# shield_lcd1.net
KiCad netlist of a schematic drawn in EAGLE
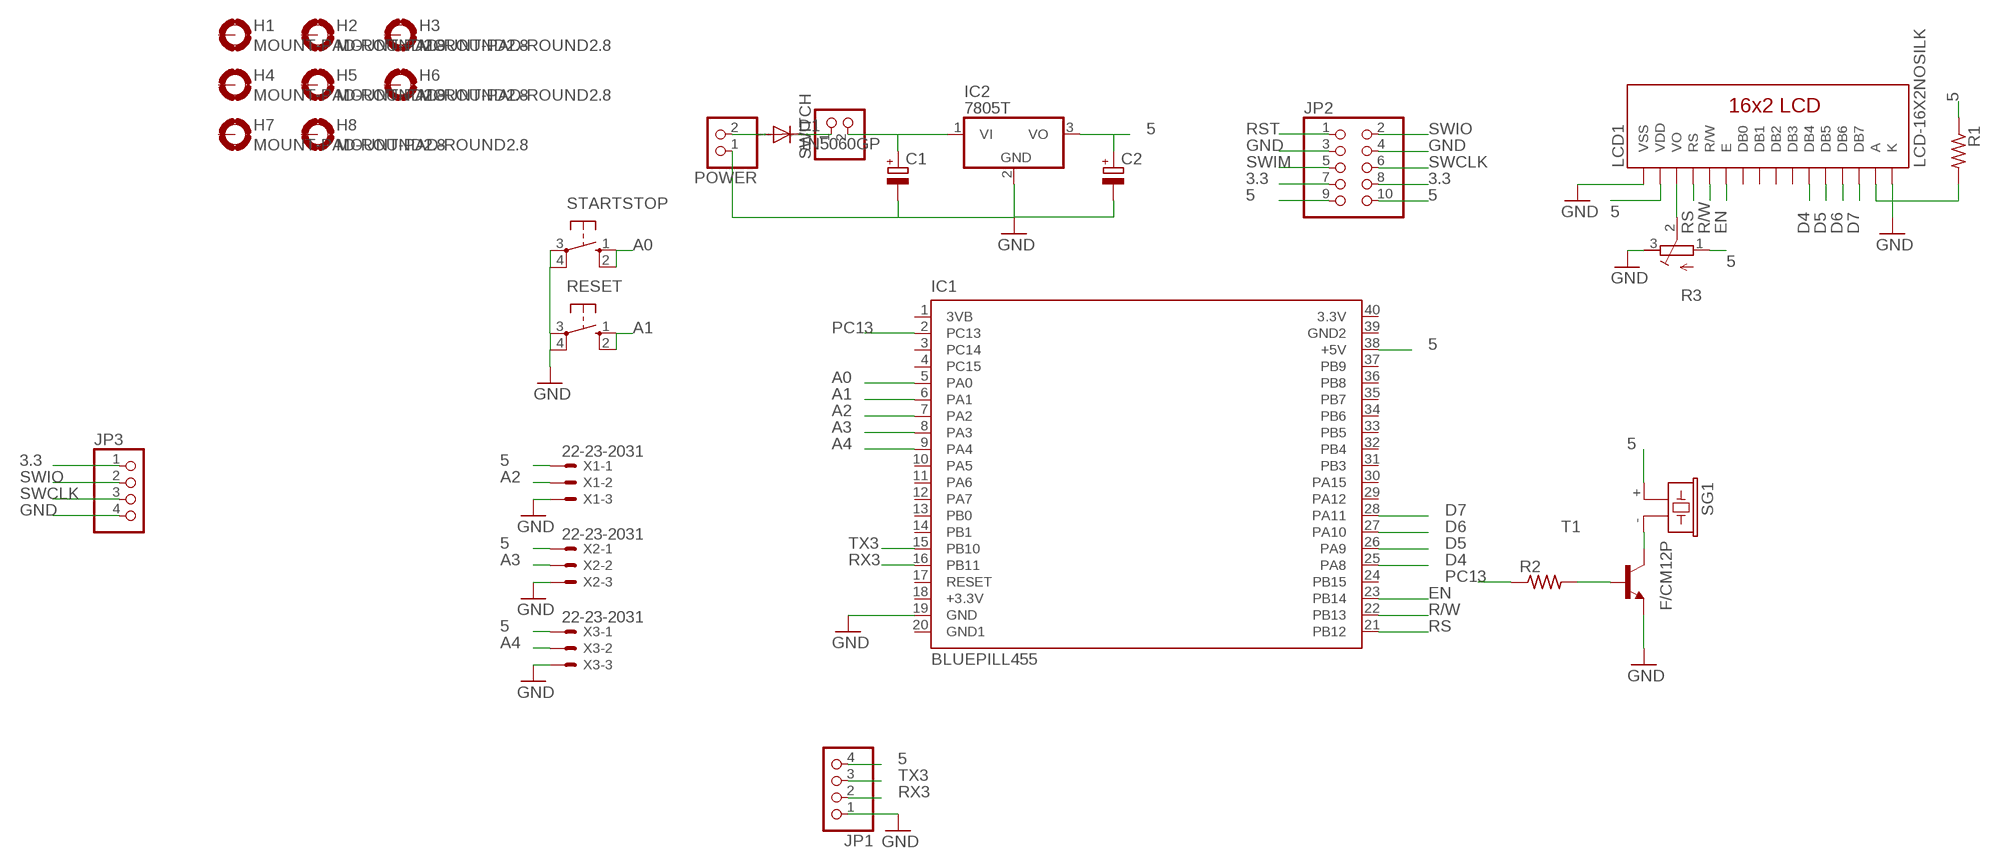
[diagram p0: schematic, sheet 1]

(export (version "E")
  (design (tool "Eeschema 10.0.6"))
  (components
    (comp (ref "C1")
      (value "CPOL-EUE2.5-7")
      (footprint "eagle-import:E2,5-7")
      (libsource (lib "eagle-import") (part "CPOL-EUE2.5-7"))
    )
    (comp (ref "C2")
      (value "CPOL-EUE2.5-6")
      (footprint "eagle-import:E2,5-6")
      (libsource (lib "eagle-import") (part "CPOL-EUE2.5-6"))
    )
    (comp (ref "D1")
      (value "1N5060GP")
      (footprint "eagle-import:DO15-12")
      (libsource (lib "eagle-import") (part "1N5060GP"))
    )
    (comp (ref "H1")
      (value "MOUNT-PAD-ROUND2.8")
      (footprint "eagle-import:2,8-PAD")
      (libsource (lib "eagle-import") (part "MOUNT-PAD-ROUND2.8"))
    )
    (comp (ref "H2")
      (value "MOUNT-PAD-ROUND2.8")
      (footprint "eagle-import:2,8-PAD")
      (libsource (lib "eagle-import") (part "MOUNT-PAD-ROUND2.8"))
    )
    (comp (ref "H3")
      (value "MOUNT-PAD-ROUND2.8")
      (footprint "eagle-import:2,8-PAD")
      (libsource (lib "eagle-import") (part "MOUNT-PAD-ROUND2.8"))
    )
    (comp (ref "H4")
      (value "MOUNT-PAD-ROUND2.8")
      (footprint "eagle-import:2,8-PAD")
      (libsource (lib "eagle-import") (part "MOUNT-PAD-ROUND2.8"))
    )
    (comp (ref "H5")
      (value "MOUNT-PAD-ROUND2.8")
      (footprint "eagle-import:2,8-PAD")
      (libsource (lib "eagle-import") (part "MOUNT-PAD-ROUND2.8"))
    )
    (comp (ref "H6")
      (value "MOUNT-PAD-ROUND2.8")
      (footprint "eagle-import:2,8-PAD")
      (libsource (lib "eagle-import") (part "MOUNT-PAD-ROUND2.8"))
    )
    (comp (ref "H7")
      (value "MOUNT-PAD-ROUND2.8")
      (footprint "eagle-import:2,8-PAD")
      (libsource (lib "eagle-import") (part "MOUNT-PAD-ROUND2.8"))
    )
    (comp (ref "H8")
      (value "MOUNT-PAD-ROUND2.8")
      (footprint "eagle-import:2,8-PAD")
      (libsource (lib "eagle-import") (part "MOUNT-PAD-ROUND2.8"))
    )
    (comp (ref "IC1")
      (value "BLUEPILL455")
      (footprint "eagle-import:DIL40")
      (fields (field (name "MF") "BluePill"))
      (libsource (lib "eagle-import") (part "BLUEPILL455"))
    )
    (comp (ref "IC2")
      (value "7805T")
      (footprint "eagle-import:TO220H")
      (libsource (lib "eagle-import") (part "78T05"))
    )
    (comp (ref "JP1")
      (value "PINHD-1X4")
      (footprint "eagle-import:1X04")
      (libsource (lib "eagle-import") (part "PINHD-1X4"))
    )
    (comp (ref "JP2")
      (value "PINHD-2X5")
      (footprint "eagle-import:2X05")
      (libsource (lib "eagle-import") (part "PINHD-2X5"))
    )
    (comp (ref "JP3")
      (value "PINHD-1X4")
      (footprint "eagle-import:1X04")
      (libsource (lib "eagle-import") (part "PINHD-1X4"))
    )
    (comp (ref "LCD1")
      (value "LCD-16X2NOSILK")
      (footprint "eagle-import:LCD-16X2_NOSILK")
      (libsource (lib "eagle-import") (part "LCD-16X2NOSILK"))
    )
    (comp (ref "POWER")
      (value "PINHD-1X2")
      (footprint "eagle-import:1X02")
      (libsource (lib "eagle-import") (part "PINHD-1X2"))
    )
    (comp (ref "R1")
      (value "R-US_0207/10")
      (footprint "eagle-import:0207_10")
      (libsource (lib "eagle-import") (part "R-US_0207/10"))
    )
    (comp (ref "R2")
      (value "R-US_M0805")
      (footprint "eagle-import:M0805")
      (libsource (lib "eagle-import") (part "R-US_M0805"))
    )
    (comp (ref "R3")
      (value "R-TRIMM3339P")
      (footprint "eagle-import:RTRIM3339P")
      (libsource (lib "eagle-import") (part "R-TRIMM3339P"))
    )
    (comp (ref "RESET")
      (value "40-XX")
      (footprint "eagle-import:B3F-40XX")
      (fields (field (name "MF") "OMRON COMPONENTS USA") (field (name "MPN") "B3F-4000"))
      (libsource (lib "eagle-import") (part "40-XX"))
    )
    (comp (ref "SG1")
      (value "F/CM12P")
      (footprint "eagle-import:F_CM12P")
      (libsource (lib "eagle-import") (part "F/CM12P"))
    )
    (comp (ref "STARTSTOP")
      (value "40-XX")
      (footprint "eagle-import:B3F-40XX")
      (fields (field (name "MF") "OMRON COMPONENTS USA") (field (name "MPN") "B3F-4000"))
      (libsource (lib "eagle-import") (part "40-XX"))
    )
    (comp (ref "SWITCH")
      (value "PINHD-1X2")
      (footprint "eagle-import:1X02")
      (libsource (lib "eagle-import") (part "PINHD-1X2"))
    )
    (comp (ref "T1")
      (value "BF820-NPN-SOT23-BEC")
      (footprint "eagle-import:SOT23-BEC")
      (libsource (lib "eagle-import") (part "-NPN-SOT23-BECBF820"))
    )
    (comp (ref "X1")
      (value "22-23-2031")
      (footprint "eagle-import:22-23-2031")
      (fields (field (name "MF") "MOLEX"))
      (libsource (lib "eagle-import") (part "22-23-2031"))
    )
    (comp (ref "X2")
      (value "22-23-2031")
      (footprint "eagle-import:22-23-2031")
      (fields (field (name "MF") "MOLEX"))
      (libsource (lib "eagle-import") (part "22-23-2031"))
    )
    (comp (ref "X3")
      (value "22-23-2031")
      (footprint "eagle-import:22-23-2031")
      (fields (field (name "MF") "MOLEX"))
      (libsource (lib "eagle-import") (part "22-23-2031"))
    )
  )
  (nets
    (net (code "1") (name "/3.3") (class "Default")
      (node (ref "JP2") (pin "7") (pinfunction "7_7") (pintype "passive"))
      (node (ref "JP2") (pin "8") (pinfunction "8_8") (pintype "passive"))
      (node (ref "JP3") (pin "1") (pinfunction "1_1") (pintype "passive"))
    )
    (net (code "2") (name "/5") (class "Default")
      (node (ref "C2") (pin "+") (pinfunction "+_+") (pintype "passive"))
      (node (ref "IC1") (pin "38") (pinfunction "+5V_38") (pintype "bidirectional"))
      (node (ref "IC2") (pin "3") (pinfunction "VO_3") (pintype "passive"))
      (node (ref "JP1") (pin "4") (pinfunction "4_4") (pintype "passive"))
      (node (ref "JP2") (pin "10") (pinfunction "10_10") (pintype "passive"))
      (node (ref "JP2") (pin "9") (pinfunction "9_9") (pintype "passive"))
      (node (ref "LCD1") (pin "2") (pinfunction "VDD_2") (pintype "power_in"))
      (node (ref "R1") (pin "1") (pinfunction "1_1") (pintype "passive"))
      (node (ref "R3") (pin "1") (pinfunction "A_1") (pintype "passive"))
      (node (ref "SG1") (pin "+") (pinfunction "1_+") (pintype "passive"))
      (node (ref "X1") (pin "1") (pinfunction "S_1") (pintype "passive"))
      (node (ref "X2") (pin "1") (pinfunction "S_1") (pintype "passive"))
      (node (ref "X3") (pin "1") (pinfunction "S_1") (pintype "passive"))
    )
    (net (code "3") (name "/A0") (class "Default")
      (node (ref "IC1") (pin "5") (pinfunction "PA0_5") (pintype "bidirectional"))
      (node (ref "STARTSTOP") (pin "1") (pinfunction "S_1") (pintype "passive"))
      (node (ref "STARTSTOP") (pin "2") (pinfunction "S1_2") (pintype "passive"))
    )
    (net (code "4") (name "/A1") (class "Default")
      (node (ref "IC1") (pin "6") (pinfunction "PA1_6") (pintype "bidirectional"))
      (node (ref "RESET") (pin "1") (pinfunction "S_1") (pintype "passive"))
      (node (ref "RESET") (pin "2") (pinfunction "S1_2") (pintype "passive"))
    )
    (net (code "5") (name "/A2") (class "Default")
      (node (ref "IC1") (pin "7") (pinfunction "PA2_7") (pintype "bidirectional"))
      (node (ref "X1") (pin "2") (pinfunction "S_2") (pintype "passive"))
    )
    (net (code "6") (name "/A3") (class "Default")
      (node (ref "IC1") (pin "8") (pinfunction "PA3_8") (pintype "bidirectional"))
      (node (ref "X2") (pin "2") (pinfunction "S_2") (pintype "passive"))
    )
    (net (code "7") (name "/A4") (class "Default")
      (node (ref "IC1") (pin "9") (pinfunction "PA4_9") (pintype "bidirectional"))
      (node (ref "X3") (pin "2") (pinfunction "S_2") (pintype "passive"))
    )
    (net (code "8") (name "/D4") (class "Default")
      (node (ref "IC1") (pin "25") (pinfunction "PA8_25") (pintype "bidirectional"))
      (node (ref "LCD1") (pin "11") (pinfunction "DB4_11") (pintype "bidirectional"))
    )
    (net (code "9") (name "/D5") (class "Default")
      (node (ref "IC1") (pin "26") (pinfunction "PA9_26") (pintype "bidirectional"))
      (node (ref "LCD1") (pin "12") (pinfunction "DB5_12") (pintype "bidirectional"))
    )
    (net (code "10") (name "/D6") (class "Default")
      (node (ref "IC1") (pin "27") (pinfunction "PA10_27") (pintype "bidirectional"))
      (node (ref "LCD1") (pin "13") (pinfunction "DB6_13") (pintype "bidirectional"))
    )
    (net (code "11") (name "/D7") (class "Default")
      (node (ref "IC1") (pin "28") (pinfunction "PA11_28") (pintype "bidirectional"))
      (node (ref "LCD1") (pin "14") (pinfunction "DB7_14") (pintype "bidirectional"))
    )
    (net (code "12") (name "/EN") (class "Default")
      (node (ref "IC1") (pin "23") (pinfunction "PB14_23") (pintype "bidirectional"))
      (node (ref "LCD1") (pin "6") (pinfunction "E_6") (pintype "input"))
    )
    (net (code "13") (name "/PA6") (class "Default")
      (node (ref "IC1") (pin "11") (pinfunction "PA6_11") (pintype "power_in"))
    )
    (net (code "14") (name "/PA7") (class "Default")
      (node (ref "IC1") (pin "12") (pinfunction "PA7_12") (pintype "power_in"))
    )
    (net (code "15") (name "/PB3") (class "Default")
      (node (ref "IC1") (pin "31") (pinfunction "PB3_31") (pintype "power_in"))
    )
    (net (code "16") (name "/PB4") (class "Default")
      (node (ref "IC1") (pin "32") (pinfunction "PB4_32") (pintype "power_in"))
    )
    (net (code "17") (name "/PC13") (class "Default")
      (node (ref "IC1") (pin "2") (pinfunction "PC13_2") (pintype "bidirectional"))
      (node (ref "R2") (pin "1") (pinfunction "1_1") (pintype "passive"))
    )
    (net (code "18") (name "/RS") (class "Default")
      (node (ref "IC1") (pin "21") (pinfunction "PB12_21") (pintype "bidirectional"))
      (node (ref "LCD1") (pin "4") (pinfunction "RS_4") (pintype "input"))
    )
    (net (code "19") (name "/RST") (class "Default")
      (node (ref "JP2") (pin "1") (pinfunction "1_1") (pintype "passive"))
    )
    (net (code "20") (name "/RX3") (class "Default")
      (node (ref "IC1") (pin "16") (pinfunction "PB11_16") (pintype "bidirectional"))
      (node (ref "JP1") (pin "2") (pinfunction "2_2") (pintype "passive"))
    )
    (net (code "21") (name "/R{slash}W") (class "Default")
      (node (ref "IC1") (pin "22") (pinfunction "PB13_22") (pintype "bidirectional"))
      (node (ref "LCD1") (pin "5") (pinfunction "R/W_5") (pintype "input"))
    )
    (net (code "22") (name "/SWCLK") (class "Default")
      (node (ref "JP2") (pin "6") (pinfunction "6_6") (pintype "passive"))
      (node (ref "JP3") (pin "3") (pinfunction "3_3") (pintype "passive"))
    )
    (net (code "23") (name "/SWIM") (class "Default")
      (node (ref "JP2") (pin "5") (pinfunction "5_5") (pintype "passive"))
    )
    (net (code "24") (name "/SWIO") (class "Default")
      (node (ref "JP2") (pin "2") (pinfunction "2_2") (pintype "passive"))
      (node (ref "JP3") (pin "2") (pinfunction "2_2") (pintype "passive"))
    )
    (net (code "25") (name "/TX3") (class "Default")
      (node (ref "IC1") (pin "15") (pinfunction "PB10_15") (pintype "bidirectional"))
      (node (ref "JP1") (pin "3") (pinfunction "3_3") (pintype "passive"))
    )
    (net (code "26") (name "GND") (class "Default")
      (node (ref "C1") (pin "-") (pinfunction "-_-") (pintype "passive"))
      (node (ref "C2") (pin "-") (pinfunction "-_-") (pintype "passive"))
      (node (ref "IC1") (pin "19") (pinfunction "GND_19") (pintype "bidirectional"))
      (node (ref "IC2") (pin "2") (pinfunction "GND_2") (pintype "passive"))
      (node (ref "JP1") (pin "1") (pinfunction "1_1") (pintype "passive"))
      (node (ref "JP2") (pin "3") (pinfunction "3_3") (pintype "passive"))
      (node (ref "JP2") (pin "4") (pinfunction "4_4") (pintype "passive"))
      (node (ref "JP3") (pin "4") (pinfunction "4_4") (pintype "passive"))
      (node (ref "LCD1") (pin "1") (pinfunction "VSS_1") (pintype "power_in"))
      (node (ref "LCD1") (pin "16") (pinfunction "K_16") (pintype "power_in"))
      (node (ref "POWER") (pin "1") (pinfunction "1_1") (pintype "passive"))
      (node (ref "R3") (pin "3") (pinfunction "E_3") (pintype "passive"))
      (node (ref "RESET") (pin "3") (pinfunction "P_3") (pintype "passive"))
      (node (ref "RESET") (pin "4") (pinfunction "P1_4") (pintype "passive"))
      (node (ref "STARTSTOP") (pin "3") (pinfunction "P_3") (pintype "passive"))
      (node (ref "STARTSTOP") (pin "4") (pinfunction "P1_4") (pintype "passive"))
      (node (ref "T1") (pin "E") (pinfunction "E_E") (pintype "passive"))
      (node (ref "X1") (pin "3") (pinfunction "S_3") (pintype "passive"))
      (node (ref "X2") (pin "3") (pinfunction "S_3") (pintype "passive"))
      (node (ref "X3") (pin "3") (pinfunction "S_3") (pintype "passive"))
    )
    (net (code "27") (name "Net-(D1-PadA)") (class "Default")
      (node (ref "D1") (pin "A") (pinfunction "A_A") (pintype "passive"))
      (node (ref "POWER") (pin "2") (pinfunction "2_2") (pintype "passive"))
    )
    (net (code "28") (name "Net-(D1-PadC)") (class "Default")
      (node (ref "D1") (pin "C") (pinfunction "C_C") (pintype "passive"))
      (node (ref "SWITCH") (pin "1") (pinfunction "1_1") (pintype "passive"))
    )
    (net (code "29") (name "Net-(IC2-VI)") (class "Default")
      (node (ref "C1") (pin "+") (pinfunction "+_+") (pintype "passive"))
      (node (ref "IC2") (pin "1") (pinfunction "VI_1") (pintype "input"))
      (node (ref "SWITCH") (pin "2") (pinfunction "2_2") (pintype "passive"))
    )
    (net (code "30") (name "Net-(LCD1-A)") (class "Default")
      (node (ref "LCD1") (pin "15") (pinfunction "A_15") (pintype "power_in"))
      (node (ref "R1") (pin "2") (pinfunction "2_2") (pintype "passive"))
    )
    (net (code "31") (name "Net-(LCD1-VO)") (class "Default")
      (node (ref "LCD1") (pin "3") (pinfunction "VO_3") (pintype "bidirectional"))
      (node (ref "R3") (pin "2") (pinfunction "S_2") (pintype "passive"))
    )
    (net (code "32") (name "Net-(R2-Pad2)") (class "Default")
      (node (ref "R2") (pin "2") (pinfunction "2_2") (pintype "passive"))
      (node (ref "T1") (pin "B") (pinfunction "B_B") (pintype "passive"))
    )
    (net (code "33") (name "Net-(SG1-2)") (class "Default")
      (node (ref "SG1") (pin "-") (pinfunction "2_-") (pintype "passive"))
      (node (ref "T1") (pin "C") (pinfunction "C_C") (pintype "passive"))
    )
    (net (code "34") (name "unconnected-(H1-MOUNT-PadB2,8)") (class "Default")
      (node (ref "H1") (pin "B2,8") (pinfunction "MOUNT_B2,8") (pintype "passive"))
    )
    (net (code "35") (name "unconnected-(H2-MOUNT-PadB2,8)") (class "Default")
      (node (ref "H2") (pin "B2,8") (pinfunction "MOUNT_B2,8") (pintype "passive"))
    )
    (net (code "36") (name "unconnected-(H3-MOUNT-PadB2,8)") (class "Default")
      (node (ref "H3") (pin "B2,8") (pinfunction "MOUNT_B2,8") (pintype "passive"))
    )
    (net (code "37") (name "unconnected-(H4-MOUNT-PadB2,8)") (class "Default")
      (node (ref "H4") (pin "B2,8") (pinfunction "MOUNT_B2,8") (pintype "passive"))
    )
    (net (code "38") (name "unconnected-(H5-MOUNT-PadB2,8)") (class "Default")
      (node (ref "H5") (pin "B2,8") (pinfunction "MOUNT_B2,8") (pintype "passive"))
    )
    (net (code "39") (name "unconnected-(H6-MOUNT-PadB2,8)") (class "Default")
      (node (ref "H6") (pin "B2,8") (pinfunction "MOUNT_B2,8") (pintype "passive"))
    )
    (net (code "40") (name "unconnected-(H7-MOUNT-PadB2,8)") (class "Default")
      (node (ref "H7") (pin "B2,8") (pinfunction "MOUNT_B2,8") (pintype "passive"))
    )
    (net (code "41") (name "unconnected-(H8-MOUNT-PadB2,8)") (class "Default")
      (node (ref "H8") (pin "B2,8") (pinfunction "MOUNT_B2,8") (pintype "passive"))
    )
    (net (code "42") (name "unconnected-(IC1-+3.3V-Pad18)") (class "Default")
      (node (ref "IC1") (pin "18") (pinfunction "+3.3V_18") (pintype "bidirectional"))
    )
    (net (code "43") (name "unconnected-(IC1-3.3V-Pad40)") (class "Default")
      (node (ref "IC1") (pin "40") (pinfunction "3.3V_40") (pintype "bidirectional"))
    )
    (net (code "44") (name "unconnected-(IC1-3VB-Pad1)") (class "Default")
      (node (ref "IC1") (pin "1") (pinfunction "3VB_1") (pintype "input"))
    )
    (net (code "45") (name "unconnected-(IC1-GND1-Pad20)") (class "Default")
      (node (ref "IC1") (pin "20") (pinfunction "GND1_20") (pintype "bidirectional"))
    )
    (net (code "46") (name "unconnected-(IC1-GND2-Pad39)") (class "Default")
      (node (ref "IC1") (pin "39") (pinfunction "GND2_39") (pintype "bidirectional"))
    )
    (net (code "47") (name "unconnected-(IC1-PA5-Pad10)") (class "Default")
      (node (ref "IC1") (pin "10") (pinfunction "PA5_10") (pintype "bidirectional"))
    )
    (net (code "48") (name "unconnected-(IC1-PA12-Pad29)") (class "Default")
      (node (ref "IC1") (pin "29") (pinfunction "PA12_29") (pintype "bidirectional"))
    )
    (net (code "49") (name "unconnected-(IC1-PA15-Pad30)") (class "Default")
      (node (ref "IC1") (pin "30") (pinfunction "PA15_30") (pintype "bidirectional"))
    )
    (net (code "50") (name "unconnected-(IC1-PB0-Pad13)") (class "Default")
      (node (ref "IC1") (pin "13") (pinfunction "PB0_13") (pintype "input"))
    )
    (net (code "51") (name "unconnected-(IC1-PB1-Pad14)") (class "Default")
      (node (ref "IC1") (pin "14") (pinfunction "PB1_14") (pintype "output"))
    )
    (net (code "52") (name "unconnected-(IC1-PB5-Pad33)") (class "Default")
      (node (ref "IC1") (pin "33") (pinfunction "PB5_33") (pintype "bidirectional"))
    )
    (net (code "53") (name "unconnected-(IC1-PB6-Pad34)") (class "Default")
      (node (ref "IC1") (pin "34") (pinfunction "PB6_34") (pintype "bidirectional"))
    )
    (net (code "54") (name "unconnected-(IC1-PB7-Pad35)") (class "Default")
      (node (ref "IC1") (pin "35") (pinfunction "PB7_35") (pintype "bidirectional"))
    )
    (net (code "55") (name "unconnected-(IC1-PB8-Pad36)") (class "Default")
      (node (ref "IC1") (pin "36") (pinfunction "PB8_36") (pintype "bidirectional"))
    )
    (net (code "56") (name "unconnected-(IC1-PB9-Pad37)") (class "Default")
      (node (ref "IC1") (pin "37") (pinfunction "PB9_37") (pintype "bidirectional"))
    )
    (net (code "57") (name "unconnected-(IC1-PB15-Pad24)") (class "Default")
      (node (ref "IC1") (pin "24") (pinfunction "PB15_24") (pintype "bidirectional"))
    )
    (net (code "58") (name "unconnected-(IC1-PC14-Pad3)") (class "Default")
      (node (ref "IC1") (pin "3") (pinfunction "PC14_3") (pintype "bidirectional"))
    )
    (net (code "59") (name "unconnected-(IC1-PC15-Pad4)") (class "Default")
      (node (ref "IC1") (pin "4") (pinfunction "PC15_4") (pintype "bidirectional"))
    )
    (net (code "60") (name "unconnected-(IC1-RESET-Pad17)") (class "Default")
      (node (ref "IC1") (pin "17") (pinfunction "RESET_17") (pintype "bidirectional"))
    )
    (net (code "61") (name "unconnected-(LCD1-DB0-Pad7)") (class "Default")
      (node (ref "LCD1") (pin "7") (pinfunction "DB0_7") (pintype "bidirectional"))
    )
    (net (code "62") (name "unconnected-(LCD1-DB1-Pad8)") (class "Default")
      (node (ref "LCD1") (pin "8") (pinfunction "DB1_8") (pintype "bidirectional"))
    )
    (net (code "63") (name "unconnected-(LCD1-DB2-Pad9)") (class "Default")
      (node (ref "LCD1") (pin "9") (pinfunction "DB2_9") (pintype "bidirectional"))
    )
    (net (code "64") (name "unconnected-(LCD1-DB3-Pad10)") (class "Default")
      (node (ref "LCD1") (pin "10") (pinfunction "DB3_10") (pintype "bidirectional"))
    )
  )
)
